# Irrigatron.net
KiCad netlist of a schematic drawn in EasyEDA
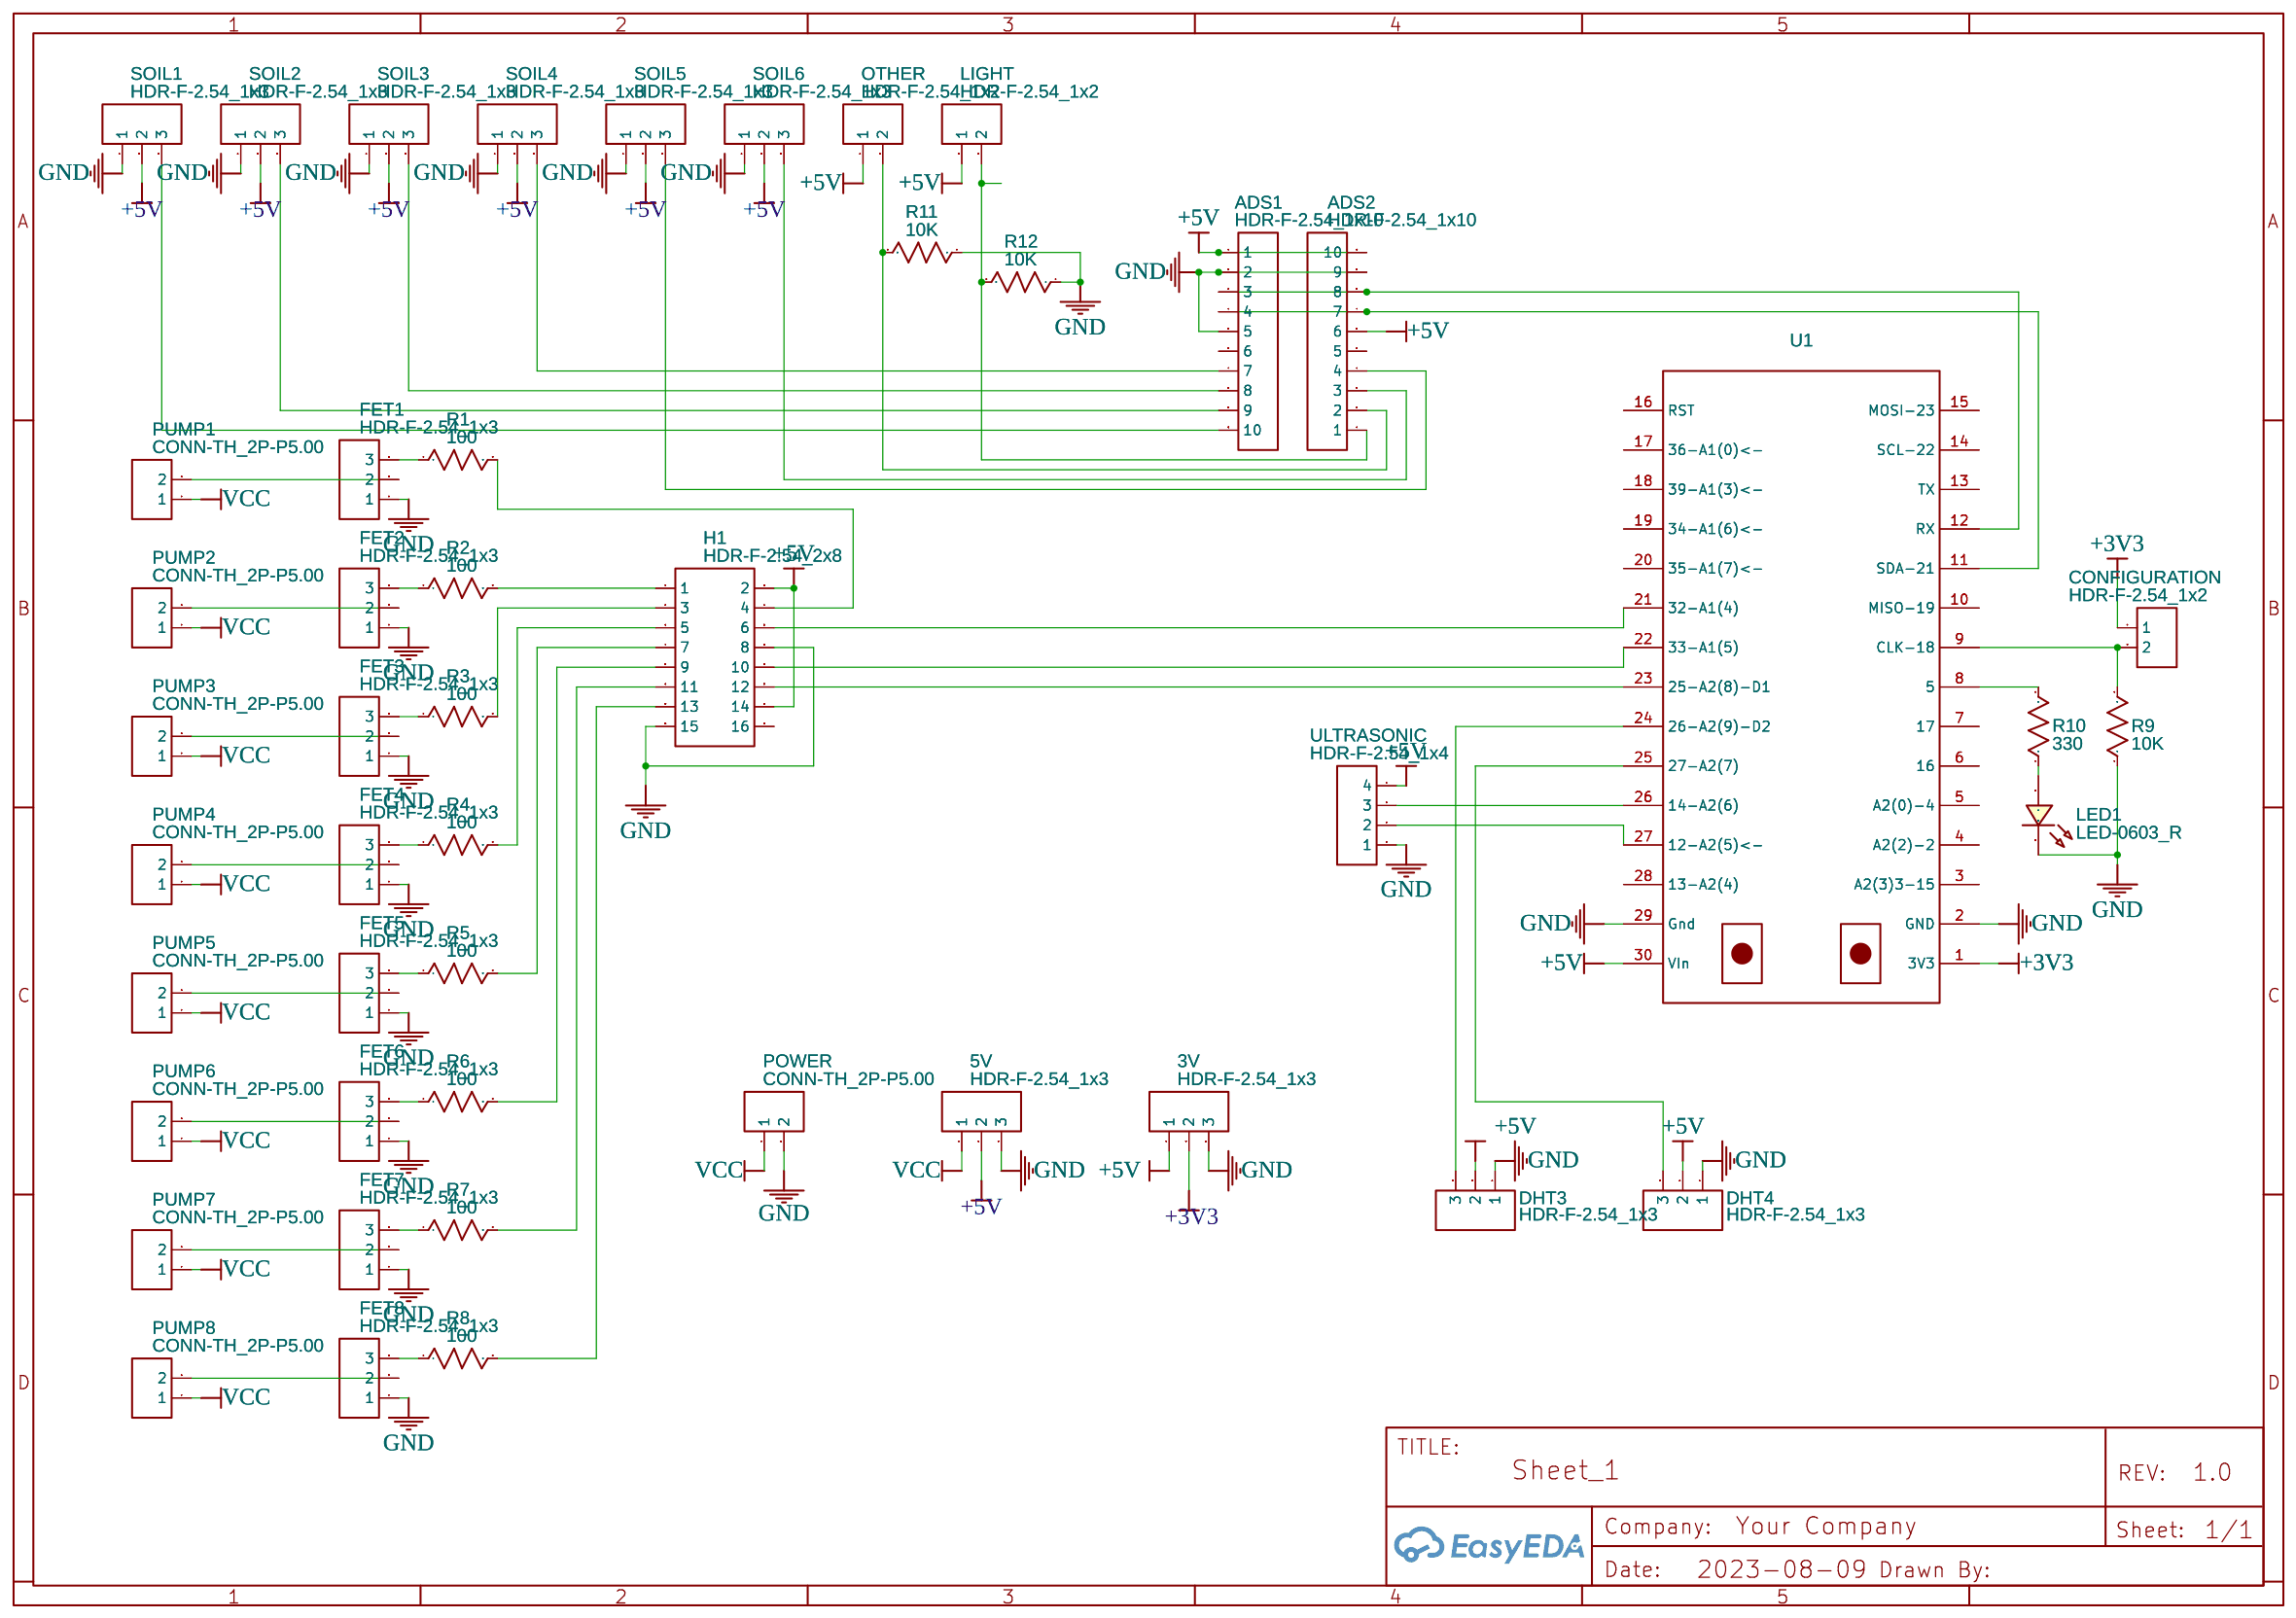
[diagram p0: schematic sheet]

(export (version "E")
  (design (tool "Eeschema 10.0.6"))
  (components
    (comp (ref "3V") (value "HDR-F-2.54_1x3") (libsource (lib "") (part "HDR-F-2.54_1x3_2")))
    (comp (ref "5V") (value "HDR-F-2.54_1x3") (libsource (lib "") (part "HDR-F-2.54_1x3_4")))
    (comp (ref "ADS1") (value "HDR-F-2.54_1x10") (libsource (lib "") (part "HDR-F-2.54_1x10")))
    (comp (ref "ADS2") (value "HDR-F-2.54_1x10") (libsource (lib "") (part "HDR-F-2.54_1x10_1")))
    (comp (ref "CONFIGURATION") (value "HDR-F-2.54_1x2") (libsource (lib "") (part "HDR-F-2.54_1x2_2")))
    (comp (ref "DHT3") (value "HDR-F-2.54_1x3") (libsource (lib "") (part "HDR-F-2.54_1x3_3")))
    (comp (ref "DHT4") (value "HDR-F-2.54_1x3") (libsource (lib "") (part "HDR-F-2.54_1x3_3")))
    (comp (ref "FET1") (value "HDR-F-2.54_1x3") (libsource (lib "") (part "HDR-F-2.54_1x3")))
    (comp (ref "FET2") (value "HDR-F-2.54_1x3") (libsource (lib "") (part "HDR-F-2.54_1x3")))
    (comp (ref "FET3") (value "HDR-F-2.54_1x3") (libsource (lib "") (part "HDR-F-2.54_1x3")))
    (comp (ref "FET4") (value "HDR-F-2.54_1x3") (libsource (lib "") (part "HDR-F-2.54_1x3")))
    (comp (ref "FET5") (value "HDR-F-2.54_1x3") (libsource (lib "") (part "HDR-F-2.54_1x3")))
    (comp (ref "FET6") (value "HDR-F-2.54_1x3") (libsource (lib "") (part "HDR-F-2.54_1x3")))
    (comp (ref "FET7") (value "HDR-F-2.54_1x3") (libsource (lib "") (part "HDR-F-2.54_1x3")))
    (comp (ref "FET8") (value "HDR-F-2.54_1x3") (libsource (lib "") (part "HDR-F-2.54_1x3")))
    (comp (ref "H1") (value "HDR-F-2.54_2x8") (libsource (lib "") (part "HDR-F-2.54_2x8")))
    (comp (ref "LED1")
      (value "LED-0603_R")
      (fields
        (field (name "Manufacturer Part") "19-217/R6C-AL1M2VY/3T")
        (field (name "Manufacturer") "EVERLIGHT(台湾亿光)")
      )
      (libsource (lib "") (part "LED-0603_R"))
    )
    (comp (ref "LIGHT") (value "HDR-F-2.54_1x2") (libsource (lib "") (part "HDR-F-2.54_1x2_1")))
    (comp (ref "OTHER") (value "HDR-F-2.54_1x2") (libsource (lib "") (part "HDR-F-2.54_1x2")))
    (comp (ref "POWER") (value "CONN-TH_2P-P5.00") (libsource (lib "") (part "CONN-TH_2P-P5.00_1")))
    (comp (ref "PUMP1") (value "CONN-TH_2P-P5.00") (libsource (lib "") (part "CONN-TH_2P-P5.00")))
    (comp (ref "PUMP2") (value "CONN-TH_2P-P5.00") (libsource (lib "") (part "CONN-TH_2P-P5.00")))
    (comp (ref "PUMP3") (value "CONN-TH_2P-P5.00") (libsource (lib "") (part "CONN-TH_2P-P5.00")))
    (comp (ref "PUMP4") (value "CONN-TH_2P-P5.00") (libsource (lib "") (part "CONN-TH_2P-P5.00")))
    (comp (ref "PUMP5") (value "CONN-TH_2P-P5.00") (libsource (lib "") (part "CONN-TH_2P-P5.00")))
    (comp (ref "PUMP6") (value "CONN-TH_2P-P5.00") (libsource (lib "") (part "CONN-TH_2P-P5.00")))
    (comp (ref "PUMP7") (value "CONN-TH_2P-P5.00") (libsource (lib "") (part "CONN-TH_2P-P5.00")))
    (comp (ref "PUMP8") (value "CONN-TH_2P-P5.00") (libsource (lib "") (part "CONN-TH_2P-P5.00")))
    (comp (ref "R1") (value "100") (libsource (lib "") (part "R_0603_US")))
    (comp (ref "R2") (value "100") (libsource (lib "") (part "R_0603_US")))
    (comp (ref "R3") (value "100") (libsource (lib "") (part "R_0603_US")))
    (comp (ref "R4") (value "100") (libsource (lib "") (part "R_0603_US")))
    (comp (ref "R5") (value "100") (libsource (lib "") (part "R_0603_US")))
    (comp (ref "R6") (value "100") (libsource (lib "") (part "R_0603_US")))
    (comp (ref "R7") (value "100") (libsource (lib "") (part "R_0603_US")))
    (comp (ref "R8") (value "100") (libsource (lib "") (part "R_0603_US")))
    (comp (ref "R9") (value "10K") (libsource (lib "") (part "R_0603_US_1")))
    (comp (ref "R10") (value "330") (libsource (lib "") (part "R_0603_US_1")))
    (comp (ref "R11") (value "10K") (libsource (lib "") (part "R_0603_US_2")))
    (comp (ref "R12") (value "10K") (libsource (lib "") (part "R_0603_US_2")))
    (comp (ref "SOIL1") (value "HDR-F-2.54_1x3") (libsource (lib "") (part "HDR-F-2.54_1x3_1")))
    (comp (ref "SOIL2") (value "HDR-F-2.54_1x3") (libsource (lib "") (part "HDR-F-2.54_1x3_1")))
    (comp (ref "SOIL3") (value "HDR-F-2.54_1x3") (libsource (lib "") (part "HDR-F-2.54_1x3_1")))
    (comp (ref "SOIL4") (value "HDR-F-2.54_1x3") (libsource (lib "") (part "HDR-F-2.54_1x3_1")))
    (comp (ref "SOIL5") (value "HDR-F-2.54_1x3") (libsource (lib "") (part "HDR-F-2.54_1x3_1")))
    (comp (ref "SOIL6") (value "HDR-F-2.54_1x3") (libsource (lib "") (part "HDR-F-2.54_1x3_1")))
    (comp (ref "U1") (value "NO") (libsource (lib "") (part "DOIT ESP32 DEVKIT V1 (30pins)")))
    (comp (ref "ULTRASONIC") (value "HDR-F-2.54_1x4") (libsource (lib "") (part "HDR-F-2.54_1x4")))
  )
  (nets
    (net (code "1") (name "+3V3") (class "Default")
      (node (ref "3V") (pin "2") (pinfunction "2_2") (pintype "input"))
      (node (ref "CONFIGURATION") (pin "1") (pinfunction "1_1") (pintype "input"))
      (node (ref "U1") (pin "1") (pinfunction "3V3_1") (pintype "unspecified"))
    )
    (net (code "2") (name "+5V") (class "Default")
      (node (ref "3V") (pin "1") (pinfunction "1_1") (pintype "input"))
      (node (ref "5V") (pin "2") (pinfunction "2_2") (pintype "input"))
      (node (ref "ADS1") (pin "1") (pinfunction "1_1") (pintype "unspecified"))
      (node (ref "ADS2") (pin "10") (pinfunction "10_10") (pintype "unspecified"))
      (node (ref "ADS2") (pin "6") (pinfunction "6_6") (pintype "unspecified"))
      (node (ref "DHT3") (pin "2") (pinfunction "2_2") (pintype "input"))
      (node (ref "DHT4") (pin "2") (pinfunction "2_2") (pintype "input"))
      (node (ref "H1") (pin "14") (pinfunction "14_14") (pintype "input"))
      (node (ref "H1") (pin "2") (pinfunction "2_2") (pintype "input"))
      (node (ref "LIGHT") (pin "1") (pinfunction "1_1") (pintype "input"))
      (node (ref "OTHER") (pin "1") (pinfunction "1_1") (pintype "input"))
      (node (ref "SOIL1") (pin "2") (pinfunction "2_2") (pintype "input"))
      (node (ref "SOIL2") (pin "2") (pinfunction "2_2") (pintype "input"))
      (node (ref "SOIL3") (pin "2") (pinfunction "2_2") (pintype "input"))
      (node (ref "SOIL4") (pin "2") (pinfunction "2_2") (pintype "input"))
      (node (ref "SOIL5") (pin "2") (pinfunction "2_2") (pintype "input"))
      (node (ref "SOIL6") (pin "2") (pinfunction "2_2") (pintype "input"))
      (node (ref "U1") (pin "30") (pinfunction "VIn_30") (pintype "unspecified"))
      (node (ref "ULTRASONIC") (pin "4") (pinfunction "4_4") (pintype "unspecified"))
    )
    (net (code "3") (name "GND") (class "Default")
      (node (ref "3V") (pin "3") (pinfunction "3_3") (pintype "input"))
      (node (ref "5V") (pin "3") (pinfunction "3_3") (pintype "input"))
      (node (ref "ADS1") (pin "2") (pinfunction "2_2") (pintype "unspecified"))
      (node (ref "ADS1") (pin "5") (pinfunction "5_5") (pintype "unspecified"))
      (node (ref "ADS2") (pin "9") (pinfunction "9_9") (pintype "unspecified"))
      (node (ref "DHT3") (pin "1") (pinfunction "1_1") (pintype "input"))
      (node (ref "DHT4") (pin "1") (pinfunction "1_1") (pintype "input"))
      (node (ref "FET1") (pin "1") (pinfunction "1_1") (pintype "input"))
      (node (ref "FET2") (pin "1") (pinfunction "1_1") (pintype "input"))
      (node (ref "FET3") (pin "1") (pinfunction "1_1") (pintype "input"))
      (node (ref "FET4") (pin "1") (pinfunction "1_1") (pintype "input"))
      (node (ref "FET5") (pin "1") (pinfunction "1_1") (pintype "input"))
      (node (ref "FET6") (pin "1") (pinfunction "1_1") (pintype "input"))
      (node (ref "FET7") (pin "1") (pinfunction "1_1") (pintype "input"))
      (node (ref "FET8") (pin "1") (pinfunction "1_1") (pintype "input"))
      (node (ref "H1") (pin "15") (pinfunction "15_15") (pintype "input"))
      (node (ref "H1") (pin "8") (pinfunction "8_8") (pintype "input"))
      (node (ref "LED1") (pin "2") (pinfunction "2_2") (pintype "unspecified"))
      (node (ref "POWER") (pin "2") (pinfunction "2_2") (pintype "unspecified"))
      (node (ref "R11") (pin "1") (pinfunction "1_1") (pintype "unspecified"))
      (node (ref "R12") (pin "1") (pinfunction "1_1") (pintype "unspecified"))
      (node (ref "R9") (pin "1") (pinfunction "1_1") (pintype "unspecified"))
      (node (ref "SOIL1") (pin "1") (pinfunction "1_1") (pintype "input"))
      (node (ref "SOIL2") (pin "1") (pinfunction "1_1") (pintype "input"))
      (node (ref "SOIL3") (pin "1") (pinfunction "1_1") (pintype "input"))
      (node (ref "SOIL4") (pin "1") (pinfunction "1_1") (pintype "input"))
      (node (ref "SOIL5") (pin "1") (pinfunction "1_1") (pintype "input"))
      (node (ref "SOIL6") (pin "1") (pinfunction "1_1") (pintype "input"))
      (node (ref "U1") (pin "2") (pinfunction "GND_2") (pintype "unspecified"))
      (node (ref "U1") (pin "29") (pinfunction "Gnd_29") (pintype "unspecified"))
      (node (ref "ULTRASONIC") (pin "1") (pinfunction "1_1") (pintype "unspecified"))
    )
    (net (code "4") (name "Net-(ADS1-Pad7)") (class "Default")
      (node (ref "ADS1") (pin "7") (pinfunction "7_7") (pintype "unspecified"))
      (node (ref "SOIL4") (pin "3") (pinfunction "3_3") (pintype "input"))
    )
    (net (code "5") (name "Net-(ADS1-Pad8)") (class "Default")
      (node (ref "ADS1") (pin "8") (pinfunction "8_8") (pintype "unspecified"))
      (node (ref "SOIL3") (pin "3") (pinfunction "3_3") (pintype "input"))
    )
    (net (code "6") (name "Net-(ADS1-Pad9)") (class "Default")
      (node (ref "ADS1") (pin "9") (pinfunction "9_9") (pintype "unspecified"))
      (node (ref "SOIL2") (pin "3") (pinfunction "3_3") (pintype "input"))
    )
    (net (code "7") (name "Net-(ADS1-Pad10)") (class "Default")
      (node (ref "ADS1") (pin "10") (pinfunction "10_10") (pintype "unspecified"))
      (node (ref "SOIL1") (pin "3") (pinfunction "3_3") (pintype "input"))
    )
    (net (code "8") (name "Net-(ADS2-Pad1)") (class "Default")
      (node (ref "ADS2") (pin "1") (pinfunction "1_1") (pintype "unspecified"))
      (node (ref "LIGHT") (pin "2") (pinfunction "2_2") (pintype "input"))
      (node (ref "R12") (pin "2") (pinfunction "2_2") (pintype "unspecified"))
    )
    (net (code "9") (name "Net-(ADS2-Pad2)") (class "Default")
      (node (ref "ADS2") (pin "2") (pinfunction "2_2") (pintype "unspecified"))
      (node (ref "OTHER") (pin "2") (pinfunction "2_2") (pintype "input"))
      (node (ref "R11") (pin "2") (pinfunction "2_2") (pintype "unspecified"))
    )
    (net (code "10") (name "Net-(ADS2-Pad3)") (class "Default")
      (node (ref "ADS2") (pin "3") (pinfunction "3_3") (pintype "unspecified"))
      (node (ref "SOIL6") (pin "3") (pinfunction "3_3") (pintype "input"))
    )
    (net (code "11") (name "Net-(ADS2-Pad4)") (class "Default")
      (node (ref "ADS2") (pin "4") (pinfunction "4_4") (pintype "unspecified"))
      (node (ref "SOIL5") (pin "3") (pinfunction "3_3") (pintype "input"))
    )
    (net (code "12") (name "Net-(FET1-Pad2)") (class "Default")
      (node (ref "FET1") (pin "2") (pinfunction "2_2") (pintype "input"))
      (node (ref "PUMP1") (pin "2") (pinfunction "2_2") (pintype "unspecified"))
    )
    (net (code "13") (name "Net-(FET1-Pad3)") (class "Default")
      (node (ref "FET1") (pin "3") (pinfunction "3_3") (pintype "input"))
      (node (ref "R1") (pin "1") (pinfunction "1_1") (pintype "unspecified"))
    )
    (net (code "14") (name "Net-(FET2-Pad2)") (class "Default")
      (node (ref "FET2") (pin "2") (pinfunction "2_2") (pintype "input"))
      (node (ref "PUMP2") (pin "2") (pinfunction "2_2") (pintype "unspecified"))
    )
    (net (code "15") (name "Net-(FET2-Pad3)") (class "Default")
      (node (ref "FET2") (pin "3") (pinfunction "3_3") (pintype "input"))
      (node (ref "R2") (pin "1") (pinfunction "1_1") (pintype "unspecified"))
    )
    (net (code "16") (name "Net-(FET3-Pad3)") (class "Default")
      (node (ref "FET3") (pin "3") (pinfunction "3_3") (pintype "input"))
      (node (ref "R3") (pin "1") (pinfunction "1_1") (pintype "unspecified"))
    )
    (net (code "17") (name "Net-(FET4-Pad2)") (class "Default")
      (node (ref "FET4") (pin "2") (pinfunction "2_2") (pintype "input"))
      (node (ref "PUMP4") (pin "2") (pinfunction "2_2") (pintype "unspecified"))
    )
    (net (code "18") (name "Net-(FET4-Pad3)") (class "Default")
      (node (ref "FET4") (pin "3") (pinfunction "3_3") (pintype "input"))
      (node (ref "R4") (pin "1") (pinfunction "1_1") (pintype "unspecified"))
    )
    (net (code "19") (name "Net-(FET5-Pad2)") (class "Default")
      (node (ref "FET5") (pin "2") (pinfunction "2_2") (pintype "input"))
      (node (ref "PUMP5") (pin "2") (pinfunction "2_2") (pintype "unspecified"))
    )
    (net (code "20") (name "Net-(FET5-Pad3)") (class "Default")
      (node (ref "FET5") (pin "3") (pinfunction "3_3") (pintype "input"))
      (node (ref "R5") (pin "1") (pinfunction "1_1") (pintype "unspecified"))
    )
    (net (code "21") (name "Net-(FET6-Pad2)") (class "Default")
      (node (ref "FET6") (pin "2") (pinfunction "2_2") (pintype "input"))
      (node (ref "PUMP6") (pin "2") (pinfunction "2_2") (pintype "unspecified"))
    )
    (net (code "22") (name "Net-(FET6-Pad3)") (class "Default")
      (node (ref "FET6") (pin "3") (pinfunction "3_3") (pintype "input"))
      (node (ref "R6") (pin "1") (pinfunction "1_1") (pintype "unspecified"))
    )
    (net (code "23") (name "Net-(FET7-Pad2)") (class "Default")
      (node (ref "FET7") (pin "2") (pinfunction "2_2") (pintype "input"))
      (node (ref "PUMP7") (pin "2") (pinfunction "2_2") (pintype "unspecified"))
    )
    (net (code "24") (name "Net-(FET7-Pad3)") (class "Default")
      (node (ref "FET7") (pin "3") (pinfunction "3_3") (pintype "input"))
      (node (ref "R7") (pin "1") (pinfunction "1_1") (pintype "unspecified"))
    )
    (net (code "25") (name "Net-(FET8-Pad2)") (class "Default")
      (node (ref "FET8") (pin "2") (pinfunction "2_2") (pintype "input"))
      (node (ref "PUMP8") (pin "2") (pinfunction "2_2") (pintype "unspecified"))
    )
    (net (code "26") (name "Net-(FET8-Pad3)") (class "Default")
      (node (ref "FET8") (pin "3") (pinfunction "3_3") (pintype "input"))
      (node (ref "R8") (pin "1") (pinfunction "1_1") (pintype "unspecified"))
    )
    (net (code "27") (name "Net-(H1-Pad1)") (class "Default")
      (node (ref "H1") (pin "1") (pinfunction "1_1") (pintype "input"))
      (node (ref "R2") (pin "2") (pinfunction "2_2") (pintype "unspecified"))
    )
    (net (code "28") (name "Net-(H1-Pad3)") (class "Default")
      (node (ref "H1") (pin "3") (pinfunction "3_3") (pintype "input"))
      (node (ref "R3") (pin "2") (pinfunction "2_2") (pintype "unspecified"))
    )
    (net (code "29") (name "Net-(H1-Pad4)") (class "Default")
      (node (ref "H1") (pin "4") (pinfunction "4_4") (pintype "input"))
      (node (ref "R1") (pin "2") (pinfunction "2_2") (pintype "unspecified"))
    )
    (net (code "30") (name "Net-(H1-Pad5)") (class "Default")
      (node (ref "H1") (pin "5") (pinfunction "5_5") (pintype "input"))
      (node (ref "R4") (pin "2") (pinfunction "2_2") (pintype "unspecified"))
    )
    (net (code "31") (name "Net-(H1-Pad7)") (class "Default")
      (node (ref "H1") (pin "7") (pinfunction "7_7") (pintype "input"))
      (node (ref "R5") (pin "2") (pinfunction "2_2") (pintype "unspecified"))
    )
    (net (code "32") (name "Net-(H1-Pad9)") (class "Default")
      (node (ref "H1") (pin "9") (pinfunction "9_9") (pintype "input"))
      (node (ref "R6") (pin "2") (pinfunction "2_2") (pintype "unspecified"))
    )
    (net (code "33") (name "Net-(H1-Pad11)") (class "Default")
      (node (ref "H1") (pin "11") (pinfunction "11_11") (pintype "input"))
      (node (ref "R7") (pin "2") (pinfunction "2_2") (pintype "unspecified"))
    )
    (net (code "34") (name "Net-(H1-Pad13)") (class "Default")
      (node (ref "H1") (pin "13") (pinfunction "13_13") (pintype "input"))
      (node (ref "R8") (pin "2") (pinfunction "2_2") (pintype "unspecified"))
    )
    (net (code "35") (name "Net-(LED1-Pad1)") (class "Default")
      (node (ref "LED1") (pin "1") (pinfunction "1_1") (pintype "unspecified"))
      (node (ref "R10") (pin "1") (pinfunction "1_1") (pintype "unspecified"))
    )
    (net (code "36") (name "Net-(U1-5)") (class "Default")
      (node (ref "R10") (pin "2") (pinfunction "2_2") (pintype "unspecified"))
      (node (ref "U1") (pin "8") (pinfunction "5_8") (pintype "unspecified"))
    )
    (net (code "37") (name "Net-(U1-12-A2(5)<-)") (class "Default")
      (node (ref "U1") (pin "27") (pinfunction "12-A2(5)<-_27") (pintype "unspecified"))
      (node (ref "ULTRASONIC") (pin "2") (pinfunction "2_2") (pintype "unspecified"))
    )
    (net (code "38") (name "Net-(U1-14-A2(6))") (class "Default")
      (node (ref "U1") (pin "26") (pinfunction "14-A2(6)_26") (pintype "unspecified"))
      (node (ref "ULTRASONIC") (pin "3") (pinfunction "3_3") (pintype "unspecified"))
    )
    (net (code "39") (name "Net-(U1-25-A2(8)-D1)") (class "Default")
      (node (ref "H1") (pin "12") (pinfunction "12_12") (pintype "input"))
      (node (ref "U1") (pin "23") (pinfunction "25-A2(8)-D1_23") (pintype "unspecified"))
    )
    (net (code "40") (name "Net-(U1-26-A2(9)-D2)") (class "Default")
      (node (ref "DHT3") (pin "3") (pinfunction "3_3") (pintype "input"))
      (node (ref "U1") (pin "24") (pinfunction "26-A2(9)-D2_24") (pintype "unspecified"))
    )
    (net (code "41") (name "Net-(U1-27-A2(7))") (class "Default")
      (node (ref "DHT4") (pin "3") (pinfunction "3_3") (pintype "input"))
      (node (ref "U1") (pin "25") (pinfunction "27-A2(7)_25") (pintype "unspecified"))
    )
    (net (code "42") (name "Net-(U1-32-A1(4))") (class "Default")
      (node (ref "H1") (pin "6") (pinfunction "6_6") (pintype "input"))
      (node (ref "U1") (pin "21") (pinfunction "32-A1(4)_21") (pintype "unspecified"))
    )
    (net (code "43") (name "Net-(U1-33-A1(5))") (class "Default")
      (node (ref "H1") (pin "10") (pinfunction "10_10") (pintype "input"))
      (node (ref "U1") (pin "22") (pinfunction "33-A1(5)_22") (pintype "unspecified"))
    )
    (net (code "44") (name "Net-(U1-CLK-18)") (class "Default")
      (node (ref "CONFIGURATION") (pin "2") (pinfunction "2_2") (pintype "input"))
      (node (ref "R9") (pin "2") (pinfunction "2_2") (pintype "unspecified"))
      (node (ref "U1") (pin "9") (pinfunction "CLK-18_9") (pintype "unspecified"))
    )
    (net (code "45") (name "Net-(U1-RX)") (class "Default")
      (node (ref "ADS1") (pin "3") (pinfunction "3_3") (pintype "unspecified"))
      (node (ref "ADS2") (pin "8") (pinfunction "8_8") (pintype "unspecified"))
      (node (ref "U1") (pin "12") (pinfunction "RX_12") (pintype "unspecified"))
    )
    (net (code "46") (name "Net-(U1-SDA-21)") (class "Default")
      (node (ref "ADS1") (pin "4") (pinfunction "4_4") (pintype "unspecified"))
      (node (ref "ADS2") (pin "7") (pinfunction "7_7") (pintype "unspecified"))
      (node (ref "U1") (pin "11") (pinfunction "SDA-21_11") (pintype "unspecified"))
    )
    (net (code "47") (name "VCC") (class "Default")
      (node (ref "5V") (pin "1") (pinfunction "1_1") (pintype "input"))
      (node (ref "POWER") (pin "1") (pinfunction "1_1") (pintype "unspecified"))
      (node (ref "PUMP1") (pin "1") (pinfunction "1_1") (pintype "unspecified"))
      (node (ref "PUMP2") (pin "1") (pinfunction "1_1") (pintype "unspecified"))
      (node (ref "PUMP3") (pin "1") (pinfunction "1_1") (pintype "unspecified"))
      (node (ref "PUMP4") (pin "1") (pinfunction "1_1") (pintype "unspecified"))
      (node (ref "PUMP5") (pin "1") (pinfunction "1_1") (pintype "unspecified"))
      (node (ref "PUMP6") (pin "1") (pinfunction "1_1") (pintype "unspecified"))
      (node (ref "PUMP7") (pin "1") (pinfunction "1_1") (pintype "unspecified"))
      (node (ref "PUMP8") (pin "1") (pinfunction "1_1") (pintype "unspecified"))
    )
    (net (code "48") (name "unconnected-(ADS1-Pad6)") (class "Default")
      (node (ref "ADS1") (pin "6") (pinfunction "6_6") (pintype "unspecified"))
    )
    (net (code "49") (name "unconnected-(ADS2-Pad5)") (class "Default")
      (node (ref "ADS2") (pin "5") (pinfunction "5_5") (pintype "unspecified"))
    )
    (net (code "50") (name "unconnected-(FET3-Pad2)") (class "Default")
      (node (ref "FET3") (pin "2") (pinfunction "2_2") (pintype "input"))
    )
    (net (code "51") (name "unconnected-(H1-Pad16)") (class "Default")
      (node (ref "H1") (pin "16") (pinfunction "16_16") (pintype "input"))
    )
    (net (code "52") (name "unconnected-(PUMP3-Pad2)") (class "Default")
      (node (ref "PUMP3") (pin "2") (pinfunction "2_2") (pintype "unspecified"))
    )
    (net (code "53") (name "unconnected-(U1-13-A2(4)-Pad28)") (class "Default")
      (node (ref "U1") (pin "28") (pinfunction "13-A2(4)_28") (pintype "unspecified"))
    )
    (net (code "54") (name "unconnected-(U1-16-Pad6)") (class "Default")
      (node (ref "U1") (pin "6") (pinfunction "16_6") (pintype "unspecified"))
    )
    (net (code "55") (name "unconnected-(U1-17-Pad7)") (class "Default")
      (node (ref "U1") (pin "7") (pinfunction "17_7") (pintype "unspecified"))
    )
    (net (code "56") (name "unconnected-(U1-34-A1(6)<--Pad19)") (class "Default")
      (node (ref "U1") (pin "19") (pinfunction "34-A1(6)<-_19") (pintype "unspecified"))
    )
    (net (code "57") (name "unconnected-(U1-35-A1(7)<--Pad20)") (class "Default")
      (node (ref "U1") (pin "20") (pinfunction "35-A1(7)<-_20") (pintype "unspecified"))
    )
    (net (code "58") (name "unconnected-(U1-36-A1(0)<--Pad17)") (class "Default")
      (node (ref "U1") (pin "17") (pinfunction "36-A1(0)<-_17") (pintype "unspecified"))
    )
    (net (code "59") (name "unconnected-(U1-39-A1(3)<--Pad18)") (class "Default")
      (node (ref "U1") (pin "18") (pinfunction "39-A1(3)<-_18") (pintype "unspecified"))
    )
    (net (code "60") (name "unconnected-(U1-A2(0)-4-Pad5)") (class "Default")
      (node (ref "U1") (pin "5") (pinfunction "A2(0)-4_5") (pintype "unspecified"))
    )
    (net (code "61") (name "unconnected-(U1-A2(2)-2-Pad4)") (class "Default")
      (node (ref "U1") (pin "4") (pinfunction "A2(2)-2_4") (pintype "unspecified"))
    )
    (net (code "62") (name "unconnected-(U1-A2(3)3-15-Pad3)") (class "Default")
      (node (ref "U1") (pin "3") (pinfunction "A2(3)3-15_3") (pintype "unspecified"))
    )
    (net (code "63") (name "unconnected-(U1-MISO-19-Pad10)") (class "Default")
      (node (ref "U1") (pin "10") (pinfunction "MISO-19_10") (pintype "unspecified"))
    )
    (net (code "64") (name "unconnected-(U1-MOSI-23-Pad15)") (class "Default")
      (node (ref "U1") (pin "15") (pinfunction "MOSI-23_15") (pintype "unspecified"))
    )
    (net (code "65") (name "unconnected-(U1-RST-Pad16)") (class "Default")
      (node (ref "U1") (pin "16") (pinfunction "RST_16") (pintype "unspecified"))
    )
    (net (code "66") (name "unconnected-(U1-SCL-22-Pad14)") (class "Default")
      (node (ref "U1") (pin "14") (pinfunction "SCL-22_14") (pintype "unspecified"))
    )
    (net (code "67") (name "unconnected-(U1-TX-Pad13)") (class "Default")
      (node (ref "U1") (pin "13") (pinfunction "TX_13") (pintype "unspecified"))
    )
  )
)
